# STM32MP1-SOM-Eth.net
KiCad netlist of a schematic drawn in Altium Designer
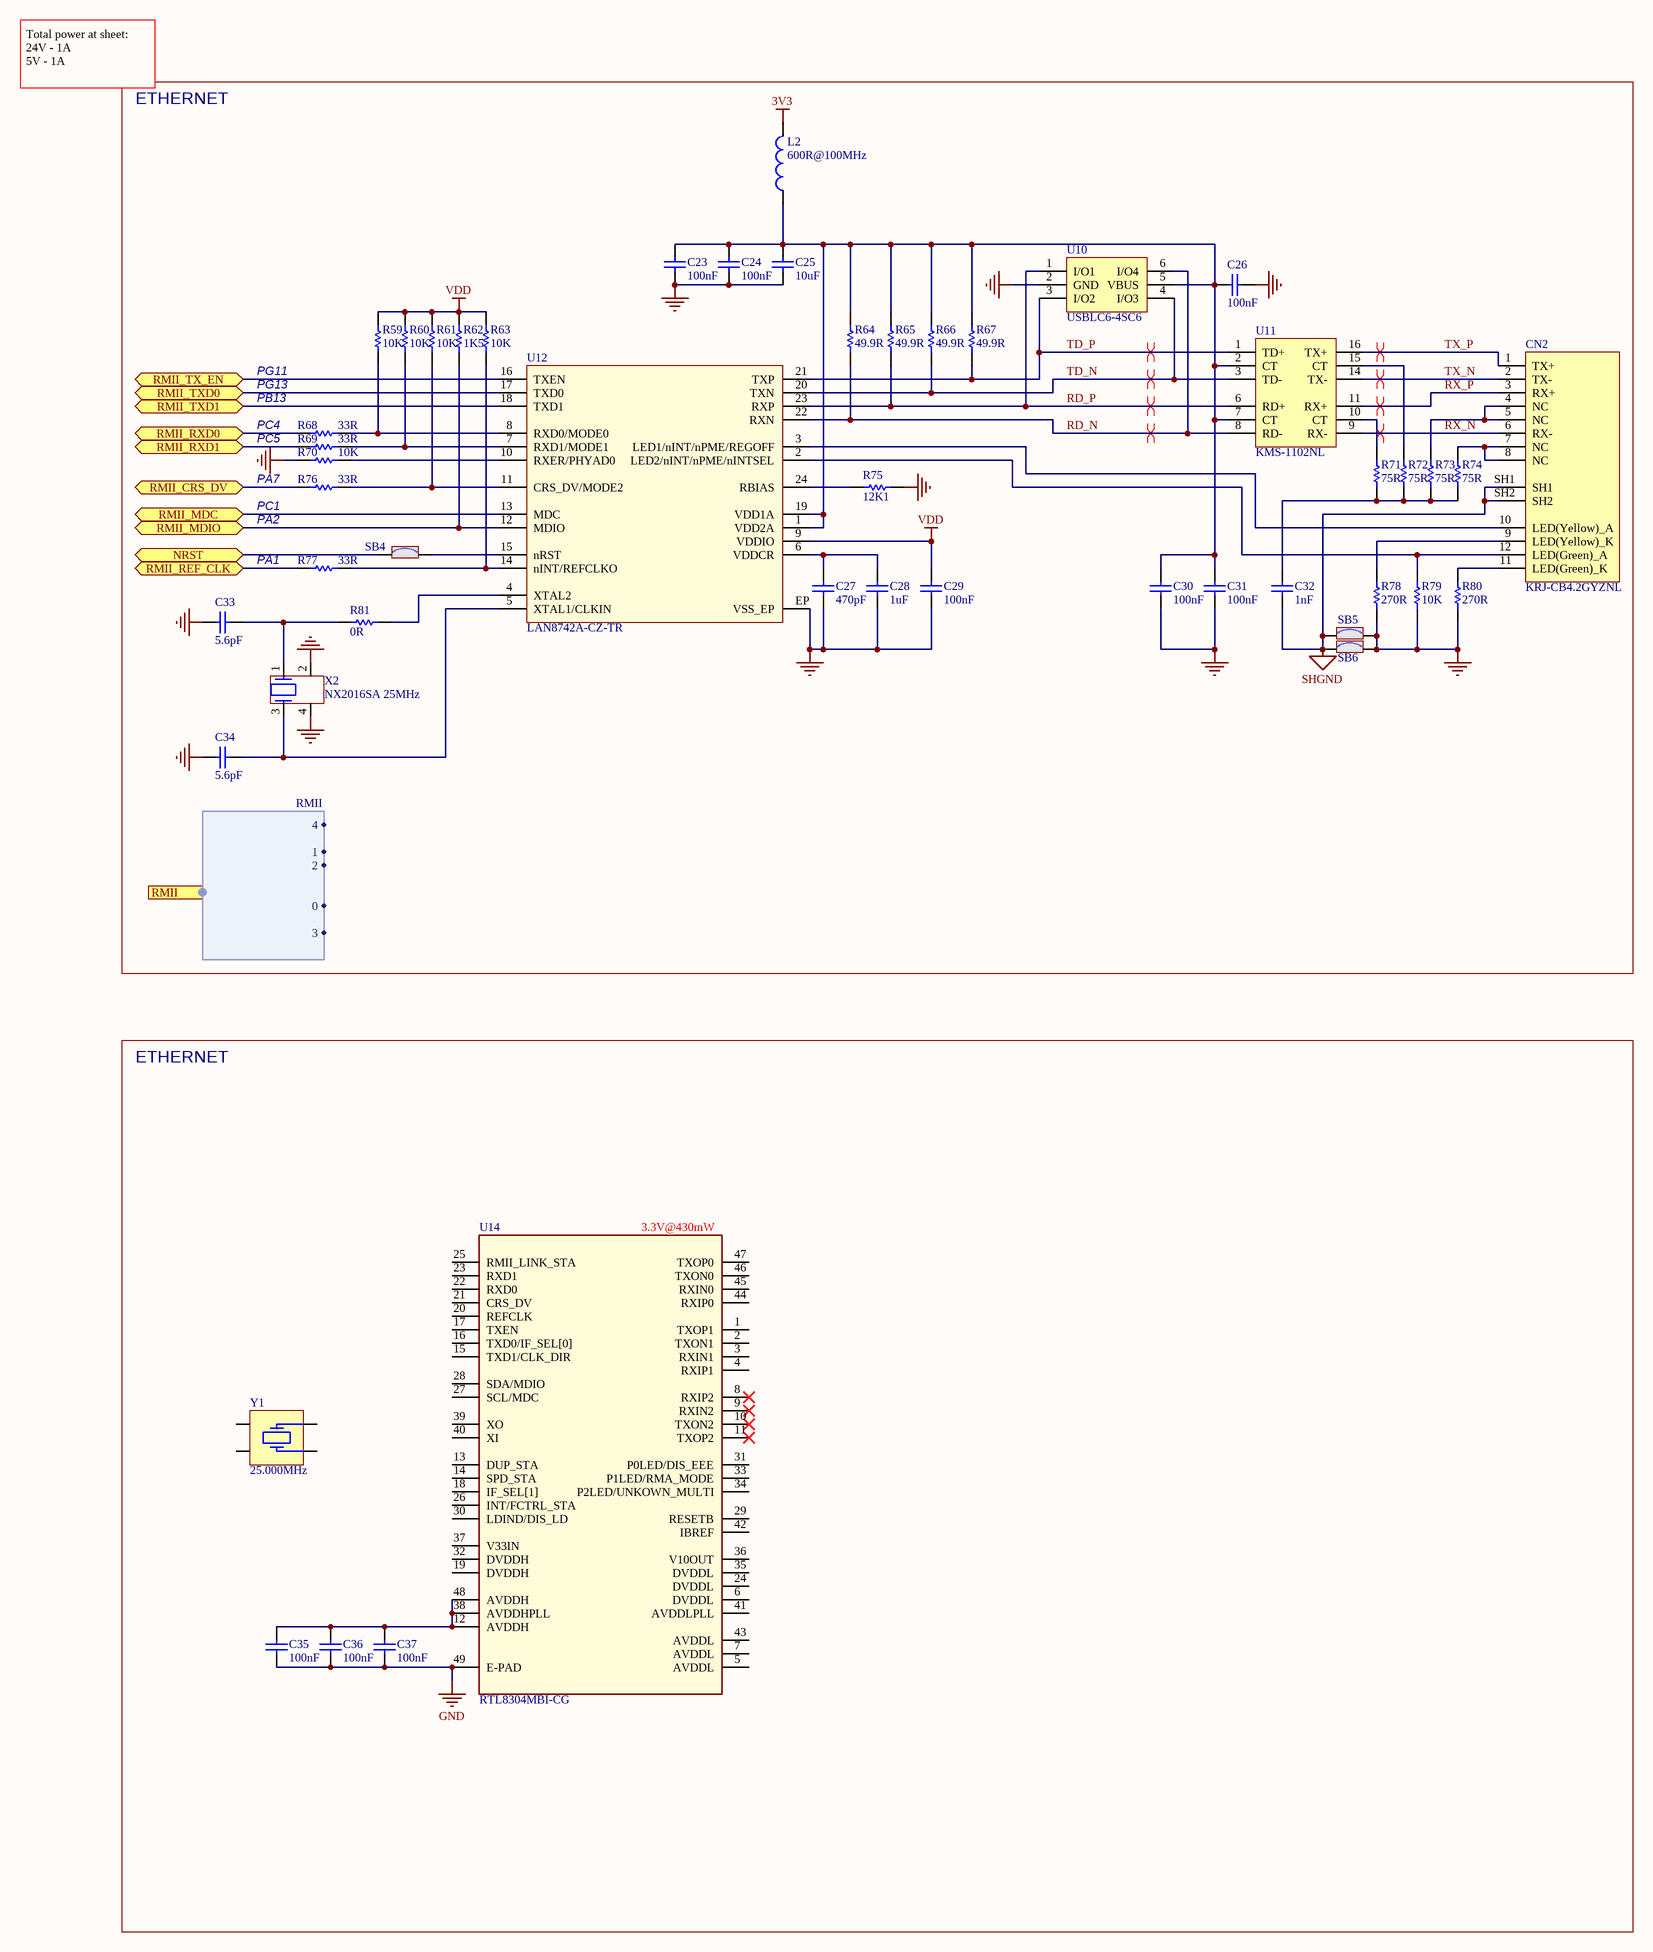
[diagram p0: STM32MP1-SOM-Eth.SchDoc]

(export (version "E")
  (design (tool "Eeschema 10.0.6"))
  (components
    (comp (ref "C23")
      (value "100nF")
      (footprint "C0603")
      (description "Capacitor, MLCC, 100nF, 6V3, X5R, 10%, 0603, T=0,8mm")
      (fields
        (field (name "INTERNAL_PART_NUMBER") "MCD-00237")
        (field (name "MANUFACTURER_PART_NUMBER") "CC0603KRX5R5BB104")
        (field (name "PROVIDED_BY") "SUBCO")
      )
      (libsource (lib "MCD_PARTS_database") (part "Capacitor"))
    )
    (comp (ref "C24")
      (value "100nF")
      (footprint "C0603")
      (description "Capacitor, MLCC, 100nF, 6V3, X5R, 10%, 0603, T=0,8mm")
      (fields
        (field (name "INTERNAL_PART_NUMBER") "MCD-00237")
        (field (name "MANUFACTURER_PART_NUMBER") "CC0603KRX5R5BB104")
        (field (name "PROVIDED_BY") "SUBCO")
      )
      (libsource (lib "MCD_PARTS_database") (part "Capacitor"))
    )
    (comp (ref "C25")
      (value "10uF")
      (footprint "C0603")
      (description "Capacitor, MLCC, 10µF, 10V, X5R, 10%, 0603, T=0.8mm")
      (fields
        (field (name "INTERNAL_PART_NUMBER") "MCD-01124")
        (field (name "MANUFACTURER_PART_NUMBER") "GRM188R61A106KAAL")
        (field (name "PROVIDED_BY") "SUBCO")
      )
      (libsource (lib "MCD_PARTS_database") (part "Capacitor"))
    )
    (comp (ref "C26")
      (value "100nF")
      (footprint "C0603")
      (description "Capacitor, MLCC, 100nF, 6V3, X5R, 10%, 0603, T=0,8mm")
      (fields
        (field (name "INTERNAL_PART_NUMBER") "MCD-00237")
        (field (name "MANUFACTURER_PART_NUMBER") "CC0603KRX5R5BB104")
        (field (name "PROVIDED_BY") "SUBCO")
      )
      (libsource (lib "MCD_PARTS_database") (part "Capacitor"))
    )
    (comp (ref "C27")
      (value "470pF")
      (footprint "C0402")
      (description "Capacitor, MLCC, 470pF, 50V, NPO, 5%, 0402, T=0,5mm")
      (fields
        (field (name "INTERNAL_PART_NUMBER") "MCD-00724")
        (field (name "MANUFACTURER_PART_NUMBER") "CC0402JRNPO9BN471")
        (field (name "PROVIDED_BY") "SUBCO")
      )
      (libsource (lib "MCD_PARTS_database") (part "Capacitor"))
    )
    (comp (ref "C28")
      (value "1uF")
      (footprint "C0402")
      (description "Capacitor, MLCC, 1uF, 6V3, X5R, 10%, 0402, T=0,5mm")
      (fields
        (field (name "INTERNAL_PART_NUMBER") "MCD-00095")
        (field (name "MANUFACTURER_PART_NUMBER") "GRM155R61E105KA12")
        (field (name "PROVIDED_BY") "SUBCO")
      )
      (libsource (lib "MCD_PARTS_database") (part "Capacitor"))
    )
    (comp (ref "C29")
      (value "100nF")
      (footprint "C0603")
      (description "Capacitor, MLCC, 100nF, 6V3, X5R, 10%, 0603, T=0,8mm")
      (fields
        (field (name "INTERNAL_PART_NUMBER") "MCD-00237")
        (field (name "MANUFACTURER_PART_NUMBER") "CC0603KRX5R5BB104")
        (field (name "PROVIDED_BY") "SUBCO")
      )
      (libsource (lib "MCD_PARTS_database") (part "Capacitor"))
    )
    (comp (ref "C30")
      (value "100nF")
      (footprint "C0603")
      (description "Capacitor, MLCC, 100nF, 6V3, X5R, 10%, 0603, T=0,8mm")
      (fields
        (field (name "INTERNAL_PART_NUMBER") "MCD-00237")
        (field (name "MANUFACTURER_PART_NUMBER") "CC0603KRX5R5BB104")
        (field (name "PROVIDED_BY") "SUBCO")
      )
      (libsource (lib "MCD_PARTS_database") (part "Capacitor"))
    )
    (comp (ref "C31")
      (value "100nF")
      (footprint "C0603")
      (description "Capacitor, MLCC, 100nF, 6V3, X5R, 10%, 0603, T=0,8mm")
      (fields
        (field (name "INTERNAL_PART_NUMBER") "MCD-00237")
        (field (name "MANUFACTURER_PART_NUMBER") "CC0603KRX5R5BB104")
        (field (name "PROVIDED_BY") "SUBCO")
      )
      (libsource (lib "MCD_PARTS_database") (part "Capacitor"))
    )
    (comp (ref "C32")
      (value "1nF")
      (footprint "C1206_H1P6")
      (description "Capacitor, MLCC, 1nF, 2KV, X7R, 10%, 1206, T=1,25mm")
      (fields
        (field (name "INTERNAL_PART_NUMBER") "MCD-00722")
        (field (name "MANUFACTURER_PART_NUMBER") "CC1206KKX7RDBB102")
        (field (name "PROVIDED_BY") "SUBCO")
      )
      (libsource (lib "MCD_PARTS_database") (part "Capacitor"))
    )
    (comp (ref "C33")
      (value "5.6pF")
      (footprint "C0402")
      (description "Capacitor, MLCC, 5.6pF, 50V, NPO, 5%, 0402, T=0,5mm")
      (fields
        (field (name "INTERNAL_PART_NUMBER") "MCD-01374")
        (field (name "MANUFACTURER_PART_NUMBER") "CC0402BRNPO9BN5R6")
        (field (name "PROVIDED_BY") "SUBCO")
      )
      (libsource (lib "MCD_PARTS_database") (part "Capacitor"))
    )
    (comp (ref "C34")
      (value "5.6pF")
      (footprint "C0402")
      (description "Capacitor, MLCC, 5.6pF, 50V, NPO, 5%, 0402, T=0,5mm")
      (fields
        (field (name "INTERNAL_PART_NUMBER") "MCD-01374")
        (field (name "MANUFACTURER_PART_NUMBER") "CC0402BRNPO9BN5R6")
        (field (name "PROVIDED_BY") "SUBCO")
      )
      (libsource (lib "MCD_PARTS_database") (part "Capacitor"))
    )
    (comp (ref "C35")
      (value "100nF")
      (footprint "C0603")
      (description "Capacitor, MLCC, 100nF, 6V3, X5R, 10%, 0603, T=0,8mm")
      (fields
        (field (name "INTERNAL_PART_NUMBER") "MCD-00237")
        (field (name "MANUFACTURER_PART_NUMBER") "CC0603KRX5R5BB104")
        (field (name "PROVIDED_BY") "SUBCO")
      )
      (libsource (lib "Motherboard") (part "Capacitor_1"))
    )
    (comp (ref "C36")
      (value "100nF")
      (footprint "C0603")
      (description "Capacitor, MLCC, 100nF, 6V3, X5R, 10%, 0603, T=0,8mm")
      (fields
        (field (name "INTERNAL_PART_NUMBER") "MCD-00237")
        (field (name "MANUFACTURER_PART_NUMBER") "CC0603KRX5R5BB104")
        (field (name "PROVIDED_BY") "SUBCO")
      )
      (libsource (lib "Motherboard") (part "Capacitor_1"))
    )
    (comp (ref "C37")
      (value "100nF")
      (footprint "C0603")
      (description "Capacitor, MLCC, 100nF, 6V3, X5R, 10%, 0603, T=0,8mm")
      (fields
        (field (name "INTERNAL_PART_NUMBER") "MCD-00237")
        (field (name "MANUFACTURER_PART_NUMBER") "CC0603KRX5R5BB104")
        (field (name "PROVIDED_BY") "SUBCO")
      )
      (libsource (lib "Motherboard") (part "Capacitor_1"))
    )
    (comp (ref "CN2")
      (value "KRJ-CB4.2GYZNL")
      (footprint "CON_RJ45_DGKYD_KRJ-CB4.2GYZNL")
      (description "RJ45 jack, single port, with LEDS, Metal shielded dip low profile")
      (fields
        (field (name "INTERNAL_PART_NUMBER") "MCD-00717")
        (field (name "MANUFACTURER") "DONGGUAN KEYOUDA ELECTRONIC TECHNOLOGY")
        (field (name "PROVIDED_BY") "SUBCO")
      )
      (libsource (lib "MCD_PARTS_database") (part "RJ45_KRJ-CB4.2GYZNL"))
    )
    (comp (ref "L2")
      (value "600R@100MHz")
      (footprint "L0603")
      (description "SMD Chip ferrite bead, 600R@100MHz +/-25%, 350mA, 500mohm DC, 0603, T=0.8mm")
      (fields
        (field (name "INTERNAL_PART_NUMBER") "MCD-00047")
        (field (name "MANUFACTURER_PART_NUMBER") "FCM1608KF-601T03")
        (field (name "PROVIDED_BY") "SUBCO")
      )
      (libsource (lib "MCD_PARTS_database") (part "BEAD"))
    )
    (comp (ref "R59")
      (value "10K")
      (footprint "R0402")
      (description "Resistor,10K,0402,1%,1/16W")
      (fields
        (field (name "INTERNAL_PART_NUMBER") "MCD-00053")
        (field (name "MANUFACTURER_PART_NUMBER") "RC0402FR-0710KL")
        (field (name "PROVIDED_BY") "SUBCO")
      )
      (libsource (lib "MCD_PARTS_database") (part "Resistor"))
    )
    (comp (ref "R60")
      (value "10K")
      (footprint "R0402")
      (description "Resistor,10K,0402,1%,1/16W")
      (fields
        (field (name "INTERNAL_PART_NUMBER") "MCD-00053")
        (field (name "MANUFACTURER_PART_NUMBER") "RC0402FR-0710KL")
        (field (name "PROVIDED_BY") "SUBCO")
      )
      (libsource (lib "MCD_PARTS_database") (part "Resistor"))
    )
    (comp (ref "R61")
      (value "10K")
      (footprint "R0402")
      (description "Resistor,10K,0402,1%,1/16W")
      (fields
        (field (name "INTERNAL_PART_NUMBER") "MCD-00053")
        (field (name "MANUFACTURER_PART_NUMBER") "RC0402FR-0710KL")
        (field (name "PROVIDED_BY") "SUBCO")
      )
      (libsource (lib "MCD_PARTS_database") (part "Resistor"))
    )
    (comp (ref "R62")
      (value "1K5")
      (footprint "R0402")
      (description "Resistor,1K5,0402,1%,1/16W")
      (fields
        (field (name "INTERNAL_PART_NUMBER") "MCD-00068")
        (field (name "MANUFACTURER_PART_NUMBER") "RC0402FR-071K5L")
        (field (name "PROVIDED_BY") "SUBCO")
      )
      (libsource (lib "MCD_PARTS_database") (part "Resistor"))
    )
    (comp (ref "R63")
      (value "10K")
      (footprint "R0402")
      (description "Resistor,10K,0402,1%,1/16W")
      (fields
        (field (name "INTERNAL_PART_NUMBER") "MCD-00053")
        (field (name "MANUFACTURER_PART_NUMBER") "RC0402FR-0710KL")
        (field (name "PROVIDED_BY") "SUBCO")
      )
      (libsource (lib "MCD_PARTS_database") (part "Resistor"))
    )
    (comp (ref "R64")
      (value "49.9R")
      (footprint "R0402")
      (description "Resistor,49R9,0402,1%,1/16W")
      (fields
        (field (name "INTERNAL_PART_NUMBER") "MCD-00565")
        (field (name "MANUFACTURER_PART_NUMBER") "RC0402FR-0749R9L")
        (field (name "PROVIDED_BY") "SUBCO")
      )
      (libsource (lib "MCD_PARTS_database") (part "Resistor"))
    )
    (comp (ref "R65")
      (value "49.9R")
      (footprint "R0402")
      (description "Resistor,49R9,0402,1%,1/16W")
      (fields
        (field (name "INTERNAL_PART_NUMBER") "MCD-00565")
        (field (name "MANUFACTURER_PART_NUMBER") "RC0402FR-0749R9L")
        (field (name "PROVIDED_BY") "SUBCO")
      )
      (libsource (lib "MCD_PARTS_database") (part "Resistor"))
    )
    (comp (ref "R66")
      (value "49.9R")
      (footprint "R0402")
      (description "Resistor,49R9,0402,1%,1/16W")
      (fields
        (field (name "INTERNAL_PART_NUMBER") "MCD-00565")
        (field (name "MANUFACTURER_PART_NUMBER") "RC0402FR-0749R9L")
        (field (name "PROVIDED_BY") "SUBCO")
      )
      (libsource (lib "MCD_PARTS_database") (part "Resistor"))
    )
    (comp (ref "R67")
      (value "49.9R")
      (footprint "R0402")
      (description "Resistor,49R9,0402,1%,1/16W")
      (fields
        (field (name "INTERNAL_PART_NUMBER") "MCD-00565")
        (field (name "MANUFACTURER_PART_NUMBER") "RC0402FR-0749R9L")
        (field (name "PROVIDED_BY") "SUBCO")
      )
      (libsource (lib "MCD_PARTS_database") (part "Resistor"))
    )
    (comp (ref "R68")
      (value "33R")
      (footprint "R0402")
      (description "Resistor,33R,0402,1%,1/16W")
      (fields
        (field (name "INTERNAL_PART_NUMBER") "MCD-00455")
        (field (name "MANUFACTURER_PART_NUMBER") "RC0402FR-0733RL")
        (field (name "PROVIDED_BY") "SUBCO")
      )
      (libsource (lib "MCD_PARTS_database") (part "Resistor"))
    )
    (comp (ref "R69")
      (value "33R")
      (footprint "R0402")
      (description "Resistor,33R,0402,1%,1/16W")
      (fields
        (field (name "INTERNAL_PART_NUMBER") "MCD-00455")
        (field (name "MANUFACTURER_PART_NUMBER") "RC0402FR-0733RL")
        (field (name "PROVIDED_BY") "SUBCO")
      )
      (libsource (lib "MCD_PARTS_database") (part "Resistor"))
    )
    (comp (ref "R70")
      (value "10K")
      (footprint "R0402")
      (description "Resistor,10K,0402,1%,1/16W")
      (fields
        (field (name "INTERNAL_PART_NUMBER") "MCD-00053")
        (field (name "MANUFACTURER_PART_NUMBER") "RC0402FR-0710KL")
        (field (name "PROVIDED_BY") "SUBCO")
      )
      (libsource (lib "MCD_PARTS_database") (part "Resistor"))
    )
    (comp (ref "R71")
      (value "75R")
      (footprint "R0402")
      (description "Resistor,75R,0402,1%,1/16W")
      (fields
        (field (name "INTERNAL_PART_NUMBER") "MCD-00515")
        (field (name "MANUFACTURER_PART_NUMBER") "RC0402FR-0775RL")
        (field (name "PROVIDED_BY") "SUBCO")
      )
      (libsource (lib "MCD_PARTS_database") (part "Resistor"))
    )
    (comp (ref "R72")
      (value "75R")
      (footprint "R0402")
      (description "Resistor,75R,0402,1%,1/16W")
      (fields
        (field (name "INTERNAL_PART_NUMBER") "MCD-00515")
        (field (name "MANUFACTURER_PART_NUMBER") "RC0402FR-0775RL")
        (field (name "PROVIDED_BY") "SUBCO")
      )
      (libsource (lib "MCD_PARTS_database") (part "Resistor"))
    )
    (comp (ref "R73")
      (value "75R")
      (footprint "R0402")
      (description "Resistor,75R,0402,1%,1/16W")
      (fields
        (field (name "INTERNAL_PART_NUMBER") "MCD-00515")
        (field (name "MANUFACTURER_PART_NUMBER") "RC0402FR-0775RL")
        (field (name "PROVIDED_BY") "SUBCO")
      )
      (libsource (lib "MCD_PARTS_database") (part "Resistor"))
    )
    (comp (ref "R74")
      (value "75R")
      (footprint "R0402")
      (description "Resistor,75R,0402,1%,1/16W")
      (fields
        (field (name "INTERNAL_PART_NUMBER") "MCD-00515")
        (field (name "MANUFACTURER_PART_NUMBER") "RC0402FR-0775RL")
        (field (name "PROVIDED_BY") "SUBCO")
      )
      (libsource (lib "MCD_PARTS_database") (part "Resistor"))
    )
    (comp (ref "R75")
      (value "12K1")
      (footprint "R0402")
      (description "Resistor,12K1,0402,1%,1/16W")
      (fields
        (field (name "INTERNAL_PART_NUMBER") "MCD-00723")
        (field (name "MANUFACTURER_PART_NUMBER") "RC0402FR-0712K1L")
        (field (name "PROVIDED_BY") "SUBCO")
      )
      (libsource (lib "MCD_PARTS_database") (part "Resistor"))
    )
    (comp (ref "R76")
      (value "33R")
      (footprint "R0402")
      (description "Resistor,33R,0402,1%,1/16W")
      (fields
        (field (name "INTERNAL_PART_NUMBER") "MCD-00455")
        (field (name "MANUFACTURER_PART_NUMBER") "RC0402FR-0733RL")
        (field (name "PROVIDED_BY") "SUBCO")
      )
      (libsource (lib "MCD_PARTS_database") (part "Resistor"))
    )
    (comp (ref "R77")
      (value "33R")
      (footprint "R0402")
      (description "Resistor,33R,0402,1%,1/16W")
      (fields
        (field (name "INTERNAL_PART_NUMBER") "MCD-00455")
        (field (name "MANUFACTURER_PART_NUMBER") "RC0402FR-0733RL")
        (field (name "PROVIDED_BY") "SUBCO")
      )
      (libsource (lib "MCD_PARTS_database") (part "Resistor"))
    )
    (comp (ref "R78")
      (value "270R")
      (footprint "R0402")
      (description "Resistor,270R,0402,1%,1/16W")
      (fields
        (field (name "INTERNAL_PART_NUMBER") "MCD-00441")
        (field (name "MANUFACTURER_PART_NUMBER") "RC0402FR-07270RL")
        (field (name "PROVIDED_BY") "SUBCO")
      )
      (libsource (lib "MCD_PARTS_database") (part "Resistor"))
    )
    (comp (ref "R79")
      (value "10K")
      (footprint "R0402")
      (description "Resistor,10K,0402,1%,1/16W")
      (fields
        (field (name "INTERNAL_PART_NUMBER") "MCD-00053")
        (field (name "MANUFACTURER_PART_NUMBER") "RC0402FR-0710KL")
        (field (name "PROVIDED_BY") "SUBCO")
      )
      (libsource (lib "MCD_PARTS_database") (part "Resistor"))
    )
    (comp (ref "R80")
      (value "270R")
      (footprint "R0402")
      (description "Resistor,270R,0402,1%,1/16W")
      (fields
        (field (name "INTERNAL_PART_NUMBER") "MCD-00441")
        (field (name "MANUFACTURER_PART_NUMBER") "RC0402FR-07270RL")
        (field (name "PROVIDED_BY") "SUBCO")
      )
      (libsource (lib "MCD_PARTS_database") (part "Resistor"))
    )
    (comp (ref "R81")
      (value "0R")
      (footprint "R0402")
      (description "Resistor,0R,0402,5%,1/16W")
      (fields
        (field (name "INTERNAL_PART_NUMBER") "MCD-00052")
        (field (name "MANUFACTURER_PART_NUMBER") "RC0402JR-070RL")
        (field (name "PROVIDED_BY") "SUBCO")
      )
      (libsource (lib "MCD_PARTS_database") (part "Resistor"))
    )
    (comp (ref "SB4")
      (value "SB_ON")
      (footprint "SOLDER-BRIDGE_R0603-0R")
      (description "Solder Bridge ON")
      (fields
        (field (name "INTERNAL_PART_NUMBER") "MCD-00071")
        (field (name "MANUFACTURER_PART_NUMBER") "RC0603JR-070RL")
        (field (name "PROVIDED_BY") "SUBCO")
      )
      (libsource (lib "MCD_PARTS_database") (part "SB_ON"))
    )
    (comp (ref "SB5")
      (value "SB_ON")
      (footprint "SOLDER-BRIDGE_R0603-0R")
      (description "Solder Bridge ON")
      (fields
        (field (name "INTERNAL_PART_NUMBER") "MCD-00071")
        (field (name "MANUFACTURER_PART_NUMBER") "RC0603JR-070RL")
        (field (name "PROVIDED_BY") "SUBCO")
      )
      (libsource (lib "MCD_PARTS_database") (part "SB_ON"))
    )
    (comp (ref "SB6")
      (value "SB_ON")
      (footprint "SOLDER-BRIDGE_R0603-0R")
      (description "Solder Bridge ON")
      (fields
        (field (name "INTERNAL_PART_NUMBER") "MCD-00071")
        (field (name "MANUFACTURER_PART_NUMBER") "RC0603JR-070RL")
        (field (name "PROVIDED_BY") "SUBCO")
      )
      (libsource (lib "MCD_PARTS_database") (part "SB_ON"))
    )
    (comp (ref "U10")
      (value "USBLC6-4SC6")
      (footprint "ESD_SOT23-6L")
      (description "Very low capacitance ESD protection , 4 lines")
      (fields
        (field (name "INTERNAL_PART_NUMBER") "MCD-00250")
        (field (name "MANUFACTURER") "STMICROELECTRONICS")
        (field (name "PROVIDED_BY") "SUBCO with ST control")
      )
      (libsource (lib "MCD_PARTS_database") (part "USBLC6-4SC6"))
    )
    (comp (ref "U11")
      (value "KMS-1102NL")
      (footprint "TRS_DGKYD_KMS-1102NL")
      (description "Discrete Magnetic Transformer Module, 16 pins, SMT, 100 Base-TX")
      (fields
        (field (name "INTERNAL_PART_NUMBER") "MCD-00718")
        (field (name "MANUFACTURER") "DONGGUAN KEYOUDA ELECTRONIC TECHNOLOGY")
        (field (name "PROVIDED_BY") "SUBCO")
      )
      (libsource (lib "MCD_PARTS_database") (part "KMS-1102NL"))
    )
    (comp (ref "U12")
      (value "LAN8742A-CZ-TR")
      (footprint "ICC_VQFN24-EPAD_4X4_P050")
      (description "10/100M RMII Ethernet transceiver")
      (fields
        (field (name "INTERNAL_PART_NUMBER") "MCD-00719")
        (field (name "MANUFACTURER") "MICROCHIP")
        (field (name "PROVIDED_BY") "SUBCO")
      )
      (libsource (lib "MCD_PARTS_database") (part "LAN8742A-CZ-TR"))
    )
    (comp (ref "U14")
      (value "RTL8304MBI-CG")
      (footprint "QFN48_SMALL_EP_7MMX7MM")
      (description "SINGLE-CHIP 4-PORT 10/100M ETHERNET SWITCH CONTROLLER")
      (fields
        (field (name "MANUFACTURER") "REALTEK")
        (field (name ".CREATOR") "MM")
        (field (name ".CHECKED PCB") "MM")
        (field (name ".CHECKED SCH") "MM")
      )
      (libsource (lib "Motherboard") (part "RTL8304MBI-CG"))
    )
    (comp (ref "X2")
      (value "NX2016SA 25MHz")
      (footprint "CRY_NX2016SA_4P")
      (description "Crystal 25MHz, 6pF, +-20ppm, 80ohms max, SMD")
      (fields
        (field (name "INTERNAL_PART_NUMBER") "MCD-01364")
        (field (name "MANUFACTURER_PART_NUMBER") "NX2016SA 25MHz EXS00A-CS11321")
        (field (name "PROVIDED_BY") "SUBCO")
      )
      (libsource (lib "MCD_PARTS_database") (part "XTAL_4_PINS"))
    )
    (comp (ref "Y1")
      (value "25.000MHz")
      (footprint "ABM8G")
      (description "CRYSTAL 25MHZ 18PF SMD")
      (fields
        (field (name "MANUFACTURER") "Abracon Corporation")
        (field (name "MANUFACTURER PART NUMBER") "ABM8G-25.000MHZ-18-D2Y-T")
        (field (name ".CHECKED PCB") "MM")
        (field (name ".CHECKED SCH") "MM")
        (field (name ".CREATOR") "MM")
      )
      (libsource (lib "Motherboard") (part "ABM8G-25.000MHZ-18-D2Y-T"))
    )
  )
  (nets
    (net (code "2") (name "/NRST") (class "Default")
      (node (ref "SB4") (pin "1") (pinfunction "1_1") (pintype "passive"))
    )
    (net (code "3") (name "/RD_N") (class "Default")
      (node (ref "R64") (pin "1") (pinfunction "1_1") (pintype "passive"))
      (node (ref "U10") (pin "6") (pinfunction "I/O4_6") (pintype "passive"))
      (node (ref "U11") (pin "8") (pinfunction "RD-_8") (pintype "passive"))
      (node (ref "U12") (pin "22") (pinfunction "RXN_22") (pintype "passive"))
    )
    (net (code "4") (name "/RD_P") (class "Default")
      (node (ref "R65") (pin "1") (pinfunction "1_1") (pintype "passive"))
      (node (ref "U10") (pin "1") (pinfunction "I/O1_1") (pintype "passive"))
      (node (ref "U11") (pin "6") (pinfunction "RD+_6") (pintype "passive"))
      (node (ref "U12") (pin "23") (pinfunction "RXP_23") (pintype "passive"))
    )
    (net (code "5") (name "/RMII_CRS_DV") (class "Default")
      (node (ref "R76") (pin "1") (pinfunction "1_1") (pintype "passive"))
    )
    (net (code "6") (name "/RMII_MDC") (class "Default")
      (node (ref "U12") (pin "13") (pinfunction "MDC_13") (pintype "passive"))
    )
    (net (code "7") (name "/RMII_MDIO") (class "Default")
      (node (ref "R62") (pin "1") (pinfunction "1_1") (pintype "passive"))
      (node (ref "U12") (pin "12") (pinfunction "MDIO_12") (pintype "passive"))
    )
    (net (code "8") (name "/RMII_REF_CLK") (class "Default")
      (node (ref "R77") (pin "1") (pinfunction "1_1") (pintype "passive"))
    )
    (net (code "9") (name "/RMII_RXD0") (class "Default")
      (node (ref "R68") (pin "1") (pinfunction "1_1") (pintype "passive"))
    )
    (net (code "10") (name "/RMII_RXD1") (class "Default")
      (node (ref "R69") (pin "1") (pinfunction "1_1") (pintype "passive"))
    )
    (net (code "11") (name "/RMII_TXD0") (class "Default")
      (node (ref "U12") (pin "17") (pinfunction "TXD0_17") (pintype "passive"))
    )
    (net (code "12") (name "/RMII_TXD1") (class "Default")
      (node (ref "U12") (pin "18") (pinfunction "TXD1_18") (pintype "passive"))
    )
    (net (code "13") (name "/RMII_TX_EN") (class "Default")
      (node (ref "U12") (pin "16") (pinfunction "TXEN_16") (pintype "passive"))
    )
    (net (code "14") (name "/RX_N") (class "Default")
      (node (ref "CN2") (pin "6") (pinfunction "RX-_6") (pintype "passive"))
      (node (ref "U11") (pin "9") (pinfunction "RX-_9") (pintype "passive"))
    )
    (net (code "15") (name "/RX_P") (class "Default")
      (node (ref "CN2") (pin "3") (pinfunction "RX+_3") (pintype "passive"))
      (node (ref "U11") (pin "11") (pinfunction "RX+_11") (pintype "passive"))
    )
    (net (code "16") (name "/TD_N") (class "Default")
      (node (ref "R66") (pin "1") (pinfunction "1_1") (pintype "passive"))
      (node (ref "U10") (pin "4") (pinfunction "I/O3_4") (pintype "passive"))
      (node (ref "U11") (pin "3") (pinfunction "TD-_3") (pintype "passive"))
      (node (ref "U12") (pin "20") (pinfunction "TXN_20") (pintype "passive"))
    )
    (net (code "17") (name "/TD_P") (class "Default")
      (node (ref "R67") (pin "1") (pinfunction "1_1") (pintype "passive"))
      (node (ref "U10") (pin "3") (pinfunction "I/O2_3") (pintype "passive"))
      (node (ref "U11") (pin "1") (pinfunction "TD+_1") (pintype "passive"))
      (node (ref "U12") (pin "21") (pinfunction "TXP_21") (pintype "passive"))
    )
    (net (code "18") (name "/TX_N") (class "Default")
      (node (ref "CN2") (pin "2") (pinfunction "TX-_2") (pintype "passive"))
      (node (ref "U11") (pin "14") (pinfunction "TX-_14") (pintype "passive"))
    )
    (net (code "19") (name "/TX_P") (class "Default")
      (node (ref "CN2") (pin "1") (pinfunction "TX+_1") (pintype "passive"))
      (node (ref "U11") (pin "16") (pinfunction "TX+_16") (pintype "passive"))
    )
    (net (code "21") (name "3V3") (class "Default")
      (node (ref "L2") (pin "2") (pinfunction "2_2") (pintype "passive"))
    )
    (net (code "22") (name "GND") (class "Default")
      (node (ref "C23") (pin "1") (pinfunction "1_1") (pintype "passive"))
      (node (ref "C24") (pin "1") (pinfunction "1_1") (pintype "passive"))
      (node (ref "C25") (pin "1") (pinfunction "1_1") (pintype "passive"))
      (node (ref "C26") (pin "2") (pinfunction "2_2") (pintype "passive"))
      (node (ref "C27") (pin "1") (pinfunction "1_1") (pintype "passive"))
      (node (ref "C28") (pin "1") (pinfunction "1_1") (pintype "passive"))
      (node (ref "C29") (pin "1") (pinfunction "1_1") (pintype "passive"))
      (node (ref "C30") (pin "1") (pinfunction "1_1") (pintype "passive"))
      (node (ref "C31") (pin "1") (pinfunction "1_1") (pintype "passive"))
      (node (ref "C33") (pin "1") (pinfunction "1_1") (pintype "passive"))
      (node (ref "C34") (pin "1") (pinfunction "1_1") (pintype "passive"))
      (node (ref "C35") (pin "1") (pinfunction "1_1") (pintype "passive"))
      (node (ref "C36") (pin "1") (pinfunction "1_1") (pintype "passive"))
      (node (ref "C37") (pin "1") (pinfunction "1_1") (pintype "passive"))
      (node (ref "R70") (pin "2") (pinfunction "2_2") (pintype "passive"))
      (node (ref "R75") (pin "2") (pinfunction "2_2") (pintype "passive"))
      (node (ref "R78") (pin "1") (pinfunction "1_1") (pintype "passive"))
      (node (ref "R79") (pin "1") (pinfunction "1_1") (pintype "passive"))
      (node (ref "R80") (pin "1") (pinfunction "1_1") (pintype "passive"))
      (node (ref "SB5") (pin "2") (pinfunction "2_2") (pintype "passive"))
      (node (ref "SB6") (pin "2") (pinfunction "2_2") (pintype "passive"))
      (node (ref "U10") (pin "2") (pinfunction "GND_2") (pintype "passive"))
      (node (ref "U12") (pin "EP") (pinfunction "VSS_EP_EP") (pintype "passive"))
      (node (ref "U14") (pin "49") (pinfunction "E-PAD_49") (pintype "passive"))
      (node (ref "X2") (pin "2") (pinfunction "2_2") (pintype "passive"))
      (node (ref "X2") (pin "4") (pinfunction "4_4") (pintype "passive"))
    )
    (net (code "23") (name "Net-(C32-Pad2)") (class "Default")
      (node (ref "C32") (pin "2") (pinfunction "2_2") (pintype "passive"))
      (node (ref "R71") (pin "1") (pinfunction "1_1") (pintype "passive"))
      (node (ref "R72") (pin "1") (pinfunction "1_1") (pintype "passive"))
      (node (ref "R73") (pin "1") (pinfunction "1_1") (pintype "passive"))
      (node (ref "R74") (pin "1") (pinfunction "1_1") (pintype "passive"))
    )
    (net (code "24") (name "Net-(C33-Pad2)") (class "Default")
      (node (ref "C33") (pin "2") (pinfunction "2_2") (pintype "passive"))
      (node (ref "R81") (pin "1") (pinfunction "1_1") (pintype "passive"))
      (node (ref "X2") (pin "1") (pinfunction "1_1") (pintype "passive"))
    )
    (net (code "25") (name "Net-(CN2-LED(Green)_A)") (class "Default")
      (node (ref "CN2") (pin "12") (pinfunction "LED(Green)_A_12") (pintype "passive"))
      (node (ref "R79") (pin "2") (pinfunction "2_2") (pintype "passive"))
      (node (ref "U12") (pin "2") (pinfunction "LED2/nINT/nPME/nINTSEL_2") (pintype "passive"))
    )
    (net (code "26") (name "Net-(CN2-LED(Green)_K)") (class "Default")
      (node (ref "CN2") (pin "11") (pinfunction "LED(Green)_K_11") (pintype "passive"))
      (node (ref "R80") (pin "2") (pinfunction "2_2") (pintype "passive"))
    )
    (net (code "27") (name "Net-(CN2-LED(Yellow)_A)") (class "Default")
      (node (ref "CN2") (pin "10") (pinfunction "LED(Yellow)_A_10") (pintype "passive"))
      (node (ref "U12") (pin "3") (pinfunction "LED1/nINT/nPME/REGOFF_3") (pintype "passive"))
    )
    (net (code "28") (name "Net-(CN2-LED(Yellow)_K)") (class "Default")
      (node (ref "CN2") (pin "9") (pinfunction "LED(Yellow)_K_9") (pintype "passive"))
      (node (ref "R78") (pin "2") (pinfunction "2_2") (pintype "passive"))
    )
    (net (code "29") (name "Net-(CN2-NC-Pad4)") (class "Default")
      (node (ref "CN2") (pin "4") (pinfunction "NC_4") (pintype "passive"))
      (node (ref "CN2") (pin "5") (pinfunction "NC_5") (pintype "passive"))
      (node (ref "R73") (pin "2") (pinfunction "2_2") (pintype "passive"))
    )
    (net (code "30") (name "Net-(CN2-NC-Pad7)") (class "Default")
      (node (ref "CN2") (pin "7") (pinfunction "NC_7") (pintype "passive"))
      (node (ref "CN2") (pin "8") (pinfunction "NC_8") (pintype "passive"))
      (node (ref "R74") (pin "2") (pinfunction "2_2") (pintype "passive"))
    )
    (net (code "31") (name "Net-(R71-Pad2)") (class "Default")
      (node (ref "R71") (pin "2") (pinfunction "2_2") (pintype "passive"))
      (node (ref "U11") (pin "10") (pinfunction "CT_10") (pintype "passive"))
    )
    (net (code "32") (name "Net-(R72-Pad2)") (class "Default")
      (node (ref "R72") (pin "2") (pinfunction "2_2") (pintype "passive"))
      (node (ref "U11") (pin "15") (pinfunction "CT_15") (pintype "passive"))
    )
    (net (code "33") (name "Net-(U10-VBUS)") (class "Default")
      (node (ref "C23") (pin "2") (pinfunction "2_2") (pintype "passive"))
      (node (ref "C24") (pin "2") (pinfunction "2_2") (pintype "passive"))
      (node (ref "C25") (pin "2") (pinfunction "2_2") (pintype "passive"))
      (node (ref "C26") (pin "1") (pinfunction "1_1") (pintype "passive"))
      (node (ref "C30") (pin "2") (pinfunction "2_2") (pintype "passive"))
      (node (ref "C31") (pin "2") (pinfunction "2_2") (pintype "passive"))
      (node (ref "L2") (pin "1") (pinfunction "1_1") (pintype "passive"))
      (node (ref "R64") (pin "2") (pinfunction "2_2") (pintype "passive"))
      (node (ref "R65") (pin "2") (pinfunction "2_2") (pintype "passive"))
      (node (ref "R66") (pin "2") (pinfunction "2_2") (pintype "passive"))
      (node (ref "R67") (pin "2") (pinfunction "2_2") (pintype "passive"))
      (node (ref "U10") (pin "5") (pinfunction "VBUS_5") (pintype "passive"))
      (node (ref "U11") (pin "2") (pinfunction "CT_2") (pintype "passive"))
      (node (ref "U11") (pin "7") (pinfunction "CT_7") (pintype "passive"))
      (node (ref "U12") (pin "1") (pinfunction "VDD2A_1") (pintype "passive"))
      (node (ref "U12") (pin "19") (pinfunction "VDD1A_19") (pintype "passive"))
    )
    (net (code "34") (name "Net-(U12-CRS_DV{slash}MODE2)") (class "Default")
      (node (ref "R61") (pin "1") (pinfunction "1_1") (pintype "passive"))
      (node (ref "R76") (pin "2") (pinfunction "2_2") (pintype "passive"))
      (node (ref "U12") (pin "11") (pinfunction "CRS_DV/MODE2_11") (pintype "passive"))
    )
    (net (code "35") (name "Net-(U12-RBIAS)") (class "Default")
      (node (ref "R75") (pin "1") (pinfunction "1_1") (pintype "passive"))
      (node (ref "U12") (pin "24") (pinfunction "RBIAS_24") (pintype "passive"))
    )
    (net (code "36") (name "Net-(U12-RXD0{slash}MODE0)") (class "Default")
      (node (ref "R59") (pin "1") (pinfunction "1_1") (pintype "passive"))
      (node (ref "R68") (pin "2") (pinfunction "2_2") (pintype "passive"))
      (node (ref "U12") (pin "8") (pinfunction "RXD0/MODE0_8") (pintype "passive"))
    )
    (net (code "37") (name "Net-(U12-RXD1{slash}MODE1)") (class "Default")
      (node (ref "R60") (pin "1") (pinfunction "1_1") (pintype "passive"))
      (node (ref "R69") (pin "2") (pinfunction "2_2") (pintype "passive"))
      (node (ref "U12") (pin "7") (pinfunction "RXD1/MODE1_7") (pintype "passive"))
    )
    (net (code "38") (name "Net-(U12-RXER{slash}PHYAD0)") (class "Default")
      (node (ref "R70") (pin "1") (pinfunction "1_1") (pintype "passive"))
      (node (ref "U12") (pin "10") (pinfunction "RXER/PHYAD0_10") (pintype "passive"))
    )
    (net (code "39") (name "Net-(U12-VDDCR)") (class "Default")
      (node (ref "C27") (pin "2") (pinfunction "2_2") (pintype "passive"))
      (node (ref "C28") (pin "2") (pinfunction "2_2") (pintype "passive"))
      (node (ref "U12") (pin "6") (pinfunction "VDDCR_6") (pintype "passive"))
    )
    (net (code "40") (name "Net-(U12-XTAL1{slash}CLKIN)") (class "Default")
      (node (ref "C34") (pin "2") (pinfunction "2_2") (pintype "passive"))
      (node (ref "U12") (pin "5") (pinfunction "XTAL1/CLKIN_5") (pintype "passive"))
      (node (ref "X2") (pin "3") (pinfunction "3_3") (pintype "passive"))
    )
    (net (code "41") (name "Net-(U12-XTAL2)") (class "Default")
      (node (ref "R81") (pin "2") (pinfunction "2_2") (pintype "passive"))
      (node (ref "U12") (pin "4") (pinfunction "XTAL2_4") (pintype "passive"))
    )
    (net (code "42") (name "Net-(U12-nINT{slash}REFCLKO)") (class "Default")
      (node (ref "R63") (pin "1") (pinfunction "1_1") (pintype "passive"))
      (node (ref "R77") (pin "2") (pinfunction "2_2") (pintype "passive"))
      (node (ref "U12") (pin "14") (pinfunction "nINT/REFCLKO_14") (pintype "passive"))
    )
    (net (code "43") (name "Net-(U12-nRST)") (class "Default")
      (node (ref "SB4") (pin "2") (pinfunction "2_2") (pintype "passive"))
      (node (ref "U12") (pin "15") (pinfunction "nRST_15") (pintype "passive"))
    )
    (net (code "44") (name "Net-(U14-AVDDHPLL)") (class "Default")
      (node (ref "C35") (pin "2") (pinfunction "2_2") (pintype "passive"))
      (node (ref "C36") (pin "2") (pinfunction "2_2") (pintype "passive"))
      (node (ref "C37") (pin "2") (pinfunction "2_2") (pintype "passive"))
      (node (ref "U14") (pin "12") (pinfunction "AVDDH_12") (pintype "passive"))
      (node (ref "U14") (pin "38") (pinfunction "AVDDHPLL_38") (pintype "passive"))
      (node (ref "U14") (pin "48") (pinfunction "AVDDH_48") (pintype "passive"))
    )
    (net (code "45") (name "SHGND") (class "Default")
      (node (ref "C32") (pin "1") (pinfunction "1_1") (pintype "passive"))
      (node (ref "CN2") (pin "SH1") (pinfunction "SH1_SH1") (pintype "passive"))
      (node (ref "CN2") (pin "SH2") (pinfunction "SH2_SH2") (pintype "passive"))
      (node (ref "SB5") (pin "1") (pinfunction "1_1") (pintype "passive"))
      (node (ref "SB6") (pin "1") (pinfunction "1_1") (pintype "passive"))
    )
    (net (code "46") (name "VDD") (class "Default")
      (node (ref "C29") (pin "2") (pinfunction "2_2") (pintype "passive"))
      (node (ref "R59") (pin "2") (pinfunction "2_2") (pintype "passive"))
      (node (ref "R60") (pin "2") (pinfunction "2_2") (pintype "passive"))
      (node (ref "R61") (pin "2") (pinfunction "2_2") (pintype "passive"))
      (node (ref "R62") (pin "2") (pinfunction "2_2") (pintype "passive"))
      (node (ref "R63") (pin "2") (pinfunction "2_2") (pintype "passive"))
      (node (ref "U12") (pin "9") (pinfunction "VDDIO_9") (pintype "passive"))
    )
    (net (code "47") (name "unconnected-(U14-AVDDL-Pad5)") (class "Default")
      (node (ref "U14") (pin "5") (pinfunction "AVDDL_5") (pintype "passive"))
    )
    (net (code "48") (name "unconnected-(U14-AVDDL-Pad7)") (class "Default")
      (node (ref "U14") (pin "7") (pinfunction "AVDDL_7") (pintype "passive"))
    )
    (net (code "49") (name "unconnected-(U14-AVDDL-Pad43)") (class "Default")
      (node (ref "U14") (pin "43") (pinfunction "AVDDL_43") (pintype "passive"))
    )
    (net (code "50") (name "unconnected-(U14-AVDDLPLL-Pad41)") (class "Default")
      (node (ref "U14") (pin "41") (pinfunction "AVDDLPLL_41") (pintype "passive"))
    )
    (net (code "51") (name "unconnected-(U14-CRS_DV-Pad21)") (class "Default")
      (node (ref "U14") (pin "21") (pinfunction "CRS_DV_21") (pintype "passive"))
    )
    (net (code "52") (name "unconnected-(U14-DUP_STA-Pad13)") (class "Default")
      (node (ref "U14") (pin "13") (pinfunction "DUP_STA_13") (pintype "passive"))
    )
    (net (code "53") (name "unconnected-(U14-DVDDH-Pad19)") (class "Default")
      (node (ref "U14") (pin "19") (pinfunction "DVDDH_19") (pintype "passive"))
    )
    (net (code "54") (name "unconnected-(U14-DVDDH-Pad32)") (class "Default")
      (node (ref "U14") (pin "32") (pinfunction "DVDDH_32") (pintype "passive"))
    )
    (net (code "55") (name "unconnected-(U14-DVDDL-Pad6)") (class "Default")
      (node (ref "U14") (pin "6") (pinfunction "DVDDL_6") (pintype "passive"))
    )
    (net (code "56") (name "unconnected-(U14-DVDDL-Pad24)") (class "Default")
      (node (ref "U14") (pin "24") (pinfunction "DVDDL_24") (pintype "passive"))
    )
    (net (code "57") (name "unconnected-(U14-DVDDL-Pad35)") (class "Default")
      (node (ref "U14") (pin "35") (pinfunction "DVDDL_35") (pintype "passive"))
    )
    (net (code "58") (name "unconnected-(U14-IBREF-Pad42)") (class "Default")
      (node (ref "U14") (pin "42") (pinfunction "IBREF_42") (pintype "passive"))
    )
    (net (code "59") (name "unconnected-(U14-IF_SEL[1]-Pad18)") (class "Default")
      (node (ref "U14") (pin "18") (pinfunction "IF_SEL[1]_18") (pintype "passive"))
    )
    (net (code "60") (name "unconnected-(U14-INT{slash}FCTRL_STA-Pad26)") (class "Default")
      (node (ref "U14") (pin "26") (pinfunction "INT/FCTRL_STA_26") (pintype "passive"))
    )
    (net (code "61") (name "unconnected-(U14-LDIND{slash}DIS_LD-Pad30)") (class "Default")
      (node (ref "U14") (pin "30") (pinfunction "LDIND/DIS_LD_30") (pintype "passive"))
    )
    (net (code "62") (name "unconnected-(U14-P0LED{slash}DIS_EEE-Pad31)") (class "Default")
      (node (ref "U14") (pin "31") (pinfunction "P0LED/DIS_EEE_31") (pintype "passive"))
    )
    (net (code "63") (name "unconnected-(U14-P1LED{slash}RMA_MODE-Pad33)") (class "Default")
      (node (ref "U14") (pin "33") (pinfunction "P1LED/RMA_MODE_33") (pintype "passive"))
    )
    (net (code "64") (name "unconnected-(U14-P2LED{slash}UNKOWN_MULTI-Pad34)") (class "Default")
      (node (ref "U14") (pin "34") (pinfunction "P2LED/UNKOWN_MULTI_34") (pintype "passive"))
    )
    (net (code "65") (name "unconnected-(U14-REFCLK-Pad20)") (class "Default")
      (node (ref "U14") (pin "20") (pinfunction "REFCLK_20") (pintype "passive"))
    )
    (net (code "66") (name "unconnected-(U14-RESETB-Pad29)") (class "Default")
      (node (ref "U14") (pin "29") (pinfunction "RESETB_29") (pintype "passive"))
    )
    (net (code "67") (name "unconnected-(U14-RMII_LINK_STA-Pad25)") (class "Default")
      (node (ref "U14") (pin "25") (pinfunction "RMII_LINK_STA_25") (pintype "passive"))
    )
    (net (code "68") (name "unconnected-(U14-RXD0-Pad22)") (class "Default")
      (node (ref "U14") (pin "22") (pinfunction "RXD0_22") (pintype "passive"))
    )
    (net (code "69") (name "unconnected-(U14-RXD1-Pad23)") (class "Default")
      (node (ref "U14") (pin "23") (pinfunction "RXD1_23") (pintype "passive"))
    )
    (net (code "70") (name "unconnected-(U14-RXIN0-Pad45)") (class "Default")
      (node (ref "U14") (pin "45") (pinfunction "RXIN0_45") (pintype "passive"))
    )
    (net (code "71") (name "unconnected-(U14-RXIN1-Pad3)") (class "Default")
      (node (ref "U14") (pin "3") (pinfunction "RXIN1_3") (pintype "passive"))
    )
    (net (code "72") (name "unconnected-(U14-RXIN2-Pad9)") (class "Default")
      (node (ref "U14") (pin "9") (pinfunction "RXIN2_9") (pintype "passive+no_connect"))
    )
    (net (code "73") (name "unconnected-(U14-RXIP0-Pad44)") (class "Default")
      (node (ref "U14") (pin "44") (pinfunction "RXIP0_44") (pintype "passive"))
    )
    (net (code "74") (name "unconnected-(U14-RXIP1-Pad4)") (class "Default")
      (node (ref "U14") (pin "4") (pinfunction "RXIP1_4") (pintype "passive"))
    )
    (net (code "75") (name "unconnected-(U14-RXIP2-Pad8)") (class "Default")
      (node (ref "U14") (pin "8") (pinfunction "RXIP2_8") (pintype "passive+no_connect"))
    )
    (net (code "76") (name "unconnected-(U14-SCL{slash}MDC-Pad27)") (class "Default")
      (node (ref "U14") (pin "27") (pinfunction "SCL/MDC_27") (pintype "passive"))
    )
    (net (code "77") (name "unconnected-(U14-SDA{slash}MDIO-Pad28)") (class "Default")
      (node (ref "U14") (pin "28") (pinfunction "SDA/MDIO_28") (pintype "passive"))
    )
    (net (code "78") (name "unconnected-(U14-SPD_STA-Pad14)") (class "Default")
      (node (ref "U14") (pin "14") (pinfunction "SPD_STA_14") (pintype "passive"))
    )
    (net (code "79") (name "unconnected-(U14-TXD0{slash}IF_SEL[0]-Pad16)") (class "Default")
      (node (ref "U14") (pin "16") (pinfunction "TXD0/IF_SEL[0]_16") (pintype "passive"))
    )
    (net (code "80") (name "unconnected-(U14-TXD1{slash}CLK_DIR-Pad15)") (class "Default")
      (node (ref "U14") (pin "15") (pinfunction "TXD1/CLK_DIR_15") (pintype "passive"))
    )
    (net (code "81") (name "unconnected-(U14-TXEN-Pad17)") (class "Default")
      (node (ref "U14") (pin "17") (pinfunction "TXEN_17") (pintype "passive"))
    )
    (net (code "82") (name "unconnected-(U14-TXON0-Pad46)") (class "Default")
      (node (ref "U14") (pin "46") (pinfunction "TXON0_46") (pintype "passive"))
    )
    (net (code "83") (name "unconnected-(U14-TXON1-Pad2)") (class "Default")
      (node (ref "U14") (pin "2") (pinfunction "TXON1_2") (pintype "passive"))
    )
    (net (code "84") (name "unconnected-(U14-TXON2-Pad10)") (class "Default")
      (node (ref "U14") (pin "10") (pinfunction "TXON2_10") (pintype "passive+no_connect"))
    )
    (net (code "85") (name "unconnected-(U14-TXOP0-Pad47)") (class "Default")
      (node (ref "U14") (pin "47") (pinfunction "TXOP0_47") (pintype "passive"))
    )
    (net (code "86") (name "unconnected-(U14-TXOP1-Pad1)") (class "Default")
      (node (ref "U14") (pin "1") (pinfunction "TXOP1_1") (pintype "passive"))
    )
    (net (code "87") (name "unconnected-(U14-TXOP2-Pad11)") (class "Default")
      (node (ref "U14") (pin "11") (pinfunction "TXOP2_11") (pintype "passive+no_connect"))
    )
    (net (code "88") (name "unconnected-(U14-V10OUT-Pad36)") (class "Default")
      (node (ref "U14") (pin "36") (pinfunction "V10OUT_36") (pintype "passive"))
    )
    (net (code "89") (name "unconnected-(U14-V33IN-Pad37)") (class "Default")
      (node (ref "U14") (pin "37") (pinfunction "V33IN_37") (pintype "passive"))
    )
    (net (code "90") (name "unconnected-(U14-XI-Pad40)") (class "Default")
      (node (ref "U14") (pin "40") (pinfunction "XI_40") (pintype "passive"))
    )
    (net (code "91") (name "unconnected-(U14-XO-Pad39)") (class "Default")
      (node (ref "U14") (pin "39") (pinfunction "XO_39") (pintype "passive"))
    )
    (net (code "92") (name "unconnected-(Y1-Pad1)") (class "Default")
      (node (ref "Y1") (pin "1") (pinfunction "1_1") (pintype "passive"))
    )
    (net (code "93") (name "unconnected-(Y1-Pad2)") (class "Default")
      (node (ref "Y1") (pin "2") (pinfunction "2_2") (pintype "passive"))
    )
    (net (code "94") (name "unconnected-(Y1-Pad3)") (class "Default")
      (node (ref "Y1") (pin "3") (pinfunction "3_3") (pintype "passive"))
    )
    (net (code "95") (name "unconnected-(Y1-Pad4)") (class "Default")
      (node (ref "Y1") (pin "4") (pinfunction "4_4") (pintype "passive"))
    )
  )
)
